# PET_Diag_Clip.net
KiCad netlist of a schematic drawn in EAGLE
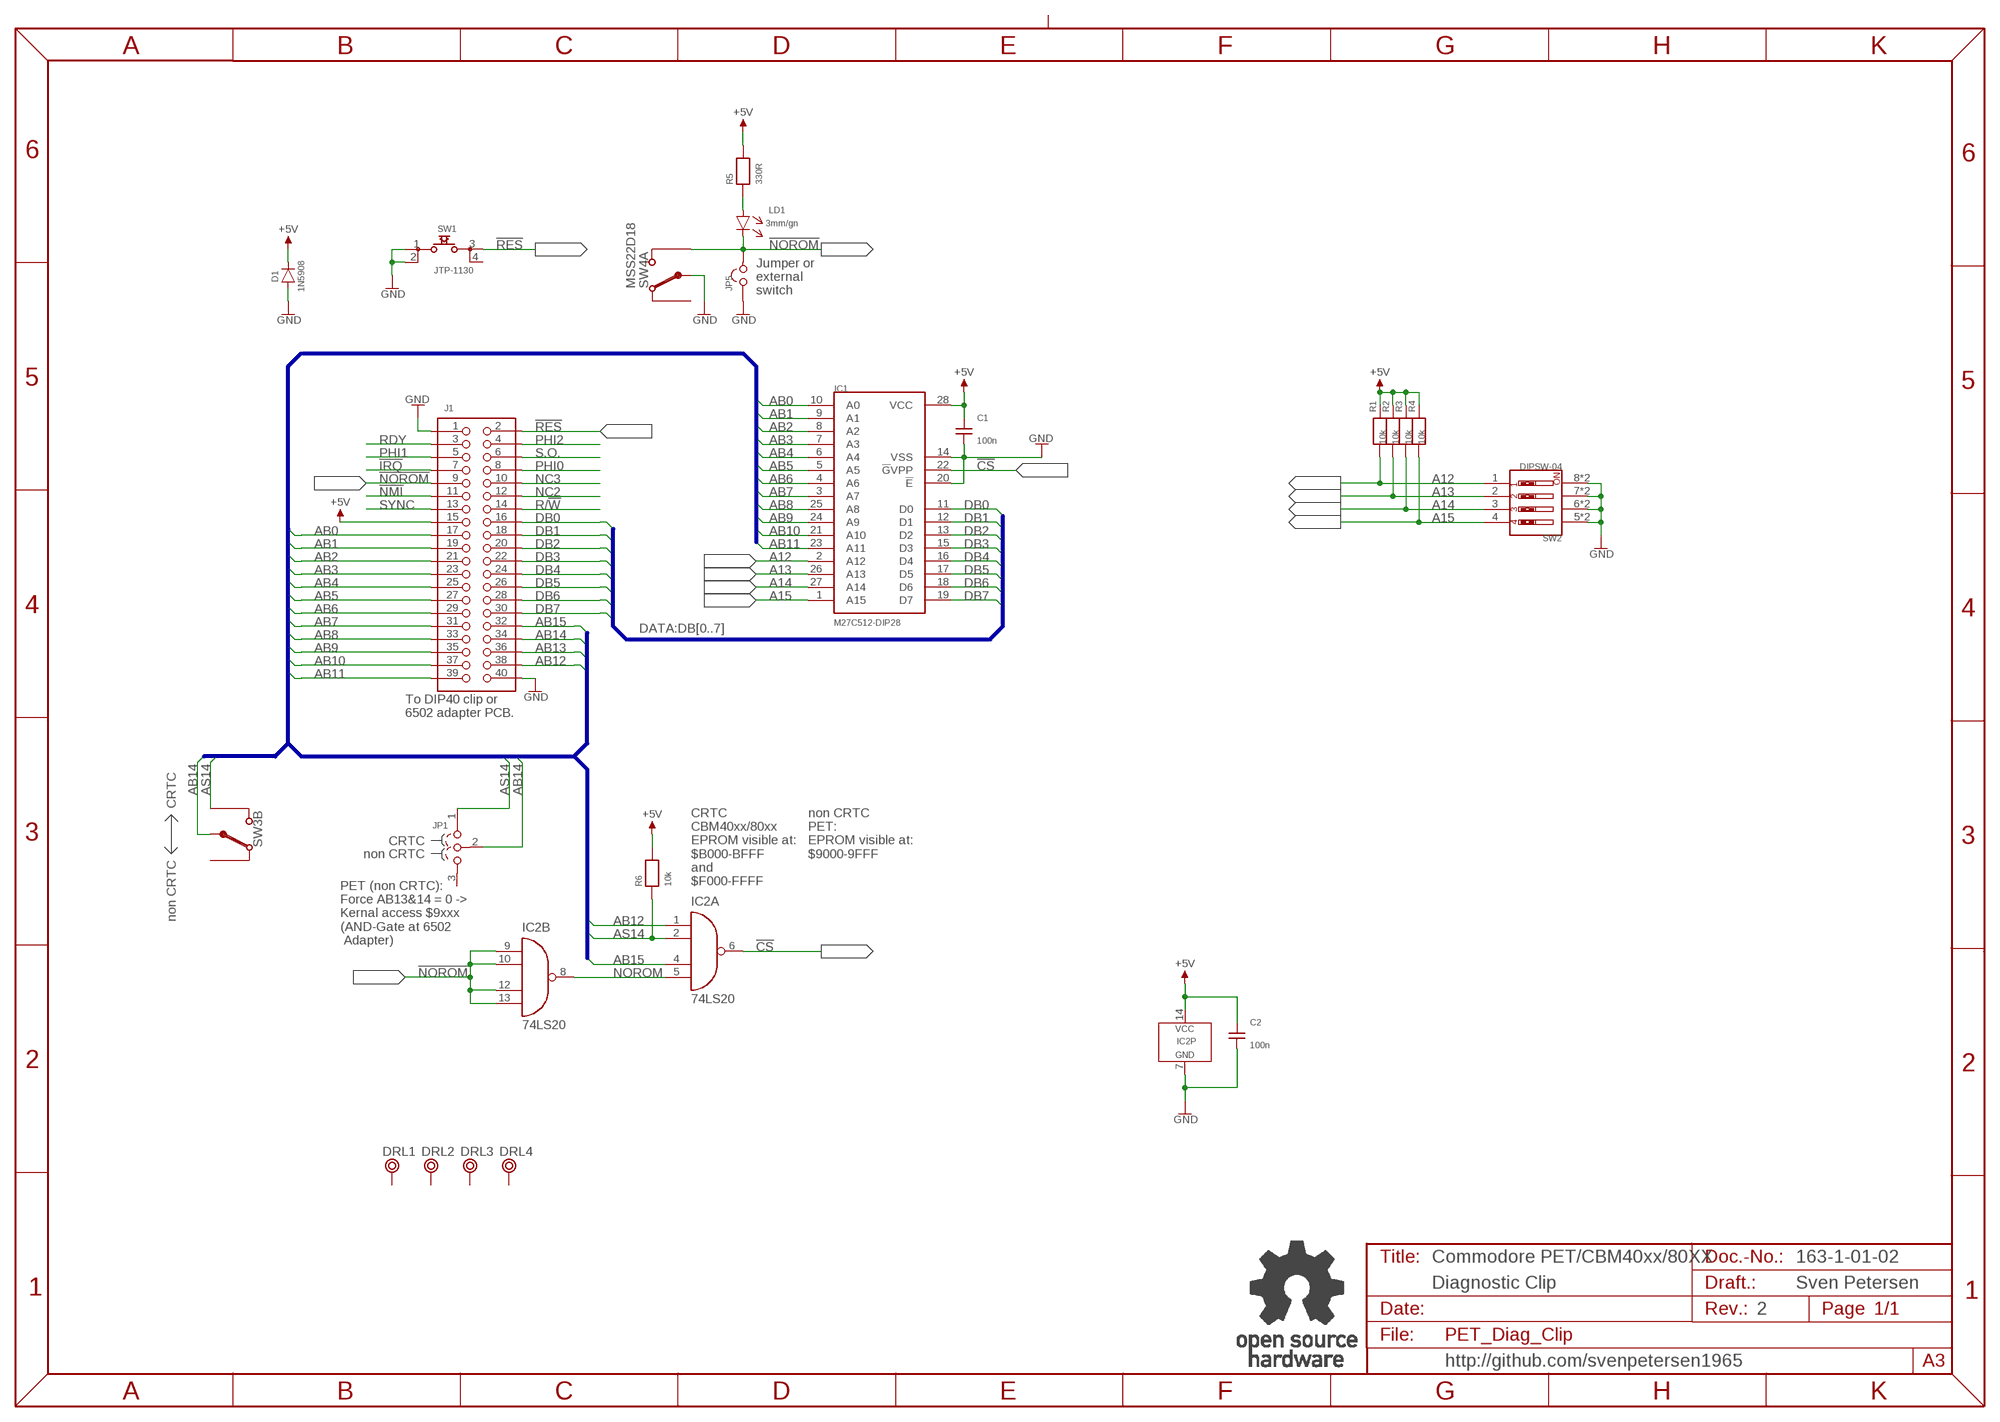
[diagram p0: schematic, sheet 1]

(export (version "E")
  (design (tool "Eeschema 10.0.6"))
  (components
    (comp (ref "C1")
      (value "100n")
      (footprint "eagle-import:C-2,5")
      (libsource (lib "eagle-import") (part "CAP01"))
    )
    (comp (ref "C2")
      (value "100n")
      (footprint "eagle-import:C-2,5")
      (libsource (lib "eagle-import") (part "CAP01"))
    )
    (comp (ref "D1")
      (value "1N5908")
      (footprint "eagle-import:DO-201")
      (libsource (lib "eagle-import") (part "1N5402"))
    )
    (comp (ref "DRL1")
      (value "BOHR3,5")
      (footprint "eagle-import:BOHR3,5")
      (libsource (lib "eagle-import") (part "BOHR3,5"))
    )
    (comp (ref "DRL2")
      (value "BOHR3,5")
      (footprint "eagle-import:BOHR3,5")
      (libsource (lib "eagle-import") (part "BOHR3,5"))
    )
    (comp (ref "DRL3")
      (value "BOHR3,5")
      (footprint "eagle-import:BOHR3,5")
      (libsource (lib "eagle-import") (part "BOHR3,5"))
    )
    (comp (ref "DRL4")
      (value "BOHR3,5")
      (footprint "eagle-import:BOHR3,5")
      (libsource (lib "eagle-import") (part "BOHR3,5"))
    )
    (comp (ref "IC1")
      (value "M27C512-DIP28")
      (footprint "eagle-import:DIL28-6")
      (libsource (lib "eagle-import") (part "M27C512-DIP28"))
    )
    (comp (ref "IC2")
      (value "74LS20")
      (footprint "eagle-import:DIL-14")
      (libsource (lib "eagle-import") (part "7420N"))
    )
    (comp (ref "J1")
      (value "PINHD-2X20WV")
      (footprint "eagle-import:2X20WV")
      (libsource (lib "eagle-import") (part "PINHD-2X20WV"))
    )
    (comp (ref "JP1")
      (value "COMBI-3P")
      (footprint "eagle-import:COMBI-3P")
      (libsource (lib "eagle-import") (part "COMBI-3P"))
    )
    (comp (ref "JP5")
      (value "JUMPER")
      (footprint "eagle-import:1X02")
      (libsource (lib "eagle-import") (part "JUMPER"))
    )
    (comp (ref "LD1")
      (value "3mm/gn")
      (footprint "eagle-import:3MM")
      (libsource (lib "eagle-import") (part "3MM"))
    )
    (comp (ref "R1")
      (value "10k")
      (footprint "eagle-import:R-10")
      (libsource (lib "eagle-import") (part "RES04"))
    )
    (comp (ref "R2")
      (value "10k")
      (footprint "eagle-import:R-10")
      (libsource (lib "eagle-import") (part "RES04"))
    )
    (comp (ref "R3")
      (value "10k")
      (footprint "eagle-import:R-10")
      (libsource (lib "eagle-import") (part "RES04"))
    )
    (comp (ref "R4")
      (value "10k")
      (footprint "eagle-import:R-10")
      (libsource (lib "eagle-import") (part "RES04"))
    )
    (comp (ref "R5")
      (value "330R")
      (footprint "eagle-import:R-10")
      (libsource (lib "eagle-import") (part "RES04"))
    )
    (comp (ref "R6")
      (value "10k")
      (footprint "eagle-import:R-10")
      (libsource (lib "eagle-import") (part "RES04"))
    )
    (comp (ref "SW1")
      (value "JTP-1130")
      (footprint "eagle-import:JTP-1130")
      (libsource (lib "eagle-import") (part "JTP-1130"))
    )
    (comp (ref "SW2")
      (value "DIPSW-04")
      (footprint "eagle-import:DIPSW-04V-COMBI")
      (libsource (lib "eagle-import") (part "DIPSW-04"))
    )
    (comp (ref "SW3")
      (value "MSS22D18")
      (footprint "eagle-import:DPDT_9MM")
      (libsource (lib "eagle-import") (part "DPDT_9MM"))
    )
    (comp (ref "SW4")
      (value "MSS22D18")
      (footprint "eagle-import:DPDT_9MM")
      (libsource (lib "eagle-import") (part "DPDT_9MM"))
    )
    (comp (ref "U$13")
      (value "OPEN_SOURCE_HW")
      (footprint "eagle-import:OPENHW")
      (libsource (lib "eagle-import") (part "OPEN_SOURCE_HW"))
    )
  )
  (nets
    (net (code "9") (name "+5V") (class "Default")
      (node (ref "C1") (pin "2") (pinfunction "2_2") (pintype "passive"))
      (node (ref "C2") (pin "2") (pinfunction "2_2") (pintype "passive"))
      (node (ref "D1") (pin "K") (pinfunction "K_K") (pintype "passive"))
      (node (ref "IC1") (pin "28") (pinfunction "VCC_28") (pintype "power_in"))
      (node (ref "IC2") (pin "14") (pinfunction "VCC_14") (pintype "bidirectional"))
      (node (ref "J1") (pin "15") (pinfunction "15_15") (pintype "passive"))
      (node (ref "R1") (pin "1") (pinfunction "1_1") (pintype "passive"))
      (node (ref "R2") (pin "1") (pinfunction "1_1") (pintype "passive"))
      (node (ref "R3") (pin "1") (pinfunction "1_1") (pintype "passive"))
      (node (ref "R4") (pin "1") (pinfunction "1_1") (pintype "passive"))
      (node (ref "R5") (pin "2") (pinfunction "2_2") (pintype "passive"))
      (node (ref "R6") (pin "2") (pinfunction "2_2") (pintype "passive"))
    )
    (net (code "10") (name "/A12") (class "Default")
      (node (ref "IC1") (pin "2") (pinfunction "A12_2") (pintype "input"))
      (node (ref "R1") (pin "2") (pinfunction "2_2") (pintype "passive"))
      (node (ref "SW2") (pin "1") (pinfunction "1_1") (pintype "passive"))
    )
    (net (code "11") (name "/A13") (class "Default")
      (node (ref "IC1") (pin "26") (pinfunction "A13_26") (pintype "input"))
      (node (ref "R2") (pin "2") (pinfunction "2_2") (pintype "passive"))
      (node (ref "SW2") (pin "2") (pinfunction "2_2") (pintype "passive"))
    )
    (net (code "12") (name "/A14") (class "Default")
      (node (ref "IC1") (pin "27") (pinfunction "A14_27") (pintype "input"))
      (node (ref "R3") (pin "2") (pinfunction "2_2") (pintype "passive"))
      (node (ref "SW2") (pin "3") (pinfunction "3_3") (pintype "passive"))
    )
    (net (code "13") (name "/A15") (class "Default")
      (node (ref "IC1") (pin "1") (pinfunction "A15_1") (pintype "input"))
      (node (ref "R4") (pin "2") (pinfunction "2_2") (pintype "passive"))
      (node (ref "SW2") (pin "4") (pinfunction "4_4") (pintype "passive"))
    )
    (net (code "14") (name "/AB0") (class "Default")
      (node (ref "IC1") (pin "10") (pinfunction "A0_10") (pintype "input"))
      (node (ref "J1") (pin "17") (pinfunction "17_17") (pintype "passive"))
    )
    (net (code "15") (name "/AB1") (class "Default")
      (node (ref "IC1") (pin "9") (pinfunction "A1_9") (pintype "input"))
      (node (ref "J1") (pin "19") (pinfunction "19_19") (pintype "passive"))
    )
    (net (code "16") (name "/AB2") (class "Default")
      (node (ref "IC1") (pin "8") (pinfunction "A2_8") (pintype "input"))
      (node (ref "J1") (pin "21") (pinfunction "21_21") (pintype "passive"))
    )
    (net (code "17") (name "/AB3") (class "Default")
      (node (ref "IC1") (pin "7") (pinfunction "A3_7") (pintype "input"))
      (node (ref "J1") (pin "23") (pinfunction "23_23") (pintype "passive"))
    )
    (net (code "18") (name "/AB4") (class "Default")
      (node (ref "IC1") (pin "6") (pinfunction "A4_6") (pintype "input"))
      (node (ref "J1") (pin "25") (pinfunction "25_25") (pintype "passive"))
    )
    (net (code "19") (name "/AB5") (class "Default")
      (node (ref "IC1") (pin "5") (pinfunction "A5_5") (pintype "input"))
      (node (ref "J1") (pin "27") (pinfunction "27_27") (pintype "passive"))
    )
    (net (code "20") (name "/AB6") (class "Default")
      (node (ref "IC1") (pin "4") (pinfunction "A6_4") (pintype "input"))
      (node (ref "J1") (pin "29") (pinfunction "29_29") (pintype "passive"))
    )
    (net (code "21") (name "/AB7") (class "Default")
      (node (ref "IC1") (pin "3") (pinfunction "A7_3") (pintype "input"))
      (node (ref "J1") (pin "31") (pinfunction "31_31") (pintype "passive"))
    )
    (net (code "22") (name "/AB8") (class "Default")
      (node (ref "IC1") (pin "25") (pinfunction "A8_25") (pintype "input"))
      (node (ref "J1") (pin "33") (pinfunction "33_33") (pintype "passive"))
    )
    (net (code "23") (name "/AB9") (class "Default")
      (node (ref "IC1") (pin "24") (pinfunction "A9_24") (pintype "input"))
      (node (ref "J1") (pin "35") (pinfunction "35_35") (pintype "passive"))
    )
    (net (code "24") (name "/AB10") (class "Default")
      (node (ref "IC1") (pin "21") (pinfunction "A10_21") (pintype "input"))
      (node (ref "J1") (pin "37") (pinfunction "37_37") (pintype "passive"))
    )
    (net (code "25") (name "/AB11") (class "Default")
      (node (ref "IC1") (pin "23") (pinfunction "A11_23") (pintype "input"))
      (node (ref "J1") (pin "39") (pinfunction "39_39") (pintype "passive"))
    )
    (net (code "26") (name "/AB12") (class "Default")
      (node (ref "IC2") (pin "1") (pinfunction "I0_1") (pintype "input"))
      (node (ref "J1") (pin "38") (pinfunction "38_38") (pintype "passive"))
    )
    (net (code "27") (name "/AB13") (class "Default")
      (node (ref "J1") (pin "36") (pinfunction "36_36") (pintype "passive"))
    )
    (net (code "28") (name "/AB14") (class "Default")
      (node (ref "J1") (pin "34") (pinfunction "34_34") (pintype "passive"))
      (node (ref "JP1") (pin "2") (pinfunction "2_2") (pintype "bidirectional"))
      (node (ref "SW3") (pin "5") (pinfunction "COM_5") (pintype "bidirectional"))
    )
    (net (code "29") (name "/AB15") (class "Default")
      (node (ref "IC2") (pin "4") (pinfunction "I2_4") (pintype "input"))
      (node (ref "J1") (pin "32") (pinfunction "32_32") (pintype "passive"))
    )
    (net (code "30") (name "/AS14") (class "Default")
      (node (ref "IC2") (pin "2") (pinfunction "I1_2") (pintype "input"))
      (node (ref "JP1") (pin "1") (pinfunction "1_1") (pintype "bidirectional"))
      (node (ref "R6") (pin "1") (pinfunction "1_1") (pintype "passive"))
      (node (ref "SW3") (pin "6") (pinfunction "UP_6") (pintype "bidirectional"))
    )
    (net (code "32") (name "/DB0") (class "Default")
      (node (ref "IC1") (pin "11") (pinfunction "D0_11") (pintype "bidirectional"))
      (node (ref "J1") (pin "16") (pinfunction "16_16") (pintype "passive"))
    )
    (net (code "33") (name "/DB1") (class "Default")
      (node (ref "IC1") (pin "12") (pinfunction "D1_12") (pintype "bidirectional"))
      (node (ref "J1") (pin "18") (pinfunction "18_18") (pintype "passive"))
    )
    (net (code "34") (name "/DB2") (class "Default")
      (node (ref "IC1") (pin "13") (pinfunction "D2_13") (pintype "bidirectional"))
      (node (ref "J1") (pin "20") (pinfunction "20_20") (pintype "passive"))
    )
    (net (code "35") (name "/DB3") (class "Default")
      (node (ref "IC1") (pin "15") (pinfunction "D3_15") (pintype "bidirectional"))
      (node (ref "J1") (pin "22") (pinfunction "22_22") (pintype "passive"))
    )
    (net (code "36") (name "/DB4") (class "Default")
      (node (ref "IC1") (pin "16") (pinfunction "D4_16") (pintype "bidirectional"))
      (node (ref "J1") (pin "24") (pinfunction "24_24") (pintype "passive"))
    )
    (net (code "37") (name "/DB5") (class "Default")
      (node (ref "IC1") (pin "17") (pinfunction "D5_17") (pintype "bidirectional"))
      (node (ref "J1") (pin "26") (pinfunction "26_26") (pintype "passive"))
    )
    (net (code "38") (name "/DB6") (class "Default")
      (node (ref "IC1") (pin "18") (pinfunction "D6_18") (pintype "bidirectional"))
      (node (ref "J1") (pin "28") (pinfunction "28_28") (pintype "passive"))
    )
    (net (code "39") (name "/DB7") (class "Default")
      (node (ref "IC1") (pin "19") (pinfunction "D7_19") (pintype "bidirectional"))
      (node (ref "J1") (pin "30") (pinfunction "30_30") (pintype "passive"))
    )
    (net (code "40") (name "/NC2") (class "Default")
      (node (ref "J1") (pin "12") (pinfunction "12_12") (pintype "passive"))
    )
    (net (code "41") (name "/NC3") (class "Default")
      (node (ref "J1") (pin "10") (pinfunction "10_10") (pintype "passive"))
    )
    (net (code "42") (name "/NOROM") (class "Default")
      (node (ref "IC2") (pin "5") (pinfunction "I3_5") (pintype "input"))
      (node (ref "IC2") (pin "8") (pinfunction "O_8") (pintype "output"))
    )
    (net (code "43") (name "/PHI0") (class "Default")
      (node (ref "J1") (pin "8") (pinfunction "8_8") (pintype "passive"))
    )
    (net (code "44") (name "/PHI1") (class "Default")
      (node (ref "J1") (pin "5") (pinfunction "5_5") (pintype "passive"))
    )
    (net (code "45") (name "/PHI2") (class "Default")
      (node (ref "J1") (pin "4") (pinfunction "4_4") (pintype "passive"))
    )
    (net (code "46") (name "/RDY") (class "Default")
      (node (ref "J1") (pin "3") (pinfunction "3_3") (pintype "passive"))
    )
    (net (code "47") (name "/R{slash}~{W}") (class "Default")
      (node (ref "J1") (pin "14") (pinfunction "14_14") (pintype "passive"))
    )
    (net (code "48") (name "/S.O.") (class "Default")
      (node (ref "J1") (pin "6") (pinfunction "6_6") (pintype "passive"))
    )
    (net (code "49") (name "/SYNC") (class "Default")
      (node (ref "J1") (pin "13") (pinfunction "13_13") (pintype "passive"))
    )
    (net (code "50") (name "/~{CS}") (class "Default")
      (node (ref "IC1") (pin "22") (pinfunction "~{G}VPP_22") (pintype "input"))
      (node (ref "IC2") (pin "6") (pinfunction "O_6") (pintype "output"))
    )
    (net (code "51") (name "/~{IRQ}") (class "Default")
      (node (ref "J1") (pin "7") (pinfunction "7_7") (pintype "passive"))
    )
    (net (code "52") (name "/~{NMI}") (class "Default")
      (node (ref "J1") (pin "11") (pinfunction "11_11") (pintype "passive"))
    )
    (net (code "53") (name "/~{NOROM}") (class "Default")
      (node (ref "IC2") (pin "10") (pinfunction "I1_10") (pintype "input"))
      (node (ref "IC2") (pin "12") (pinfunction "I2_12") (pintype "input"))
      (node (ref "IC2") (pin "13") (pinfunction "I3_13") (pintype "input"))
      (node (ref "IC2") (pin "9") (pinfunction "I0_9") (pintype "input"))
      (node (ref "J1") (pin "9") (pinfunction "9_9") (pintype "passive"))
      (node (ref "JP5") (pin "2") (pinfunction "2_2") (pintype "bidirectional"))
      (node (ref "LD1") (pin "C") (pinfunction "K_C") (pintype "bidirectional"))
      (node (ref "SW4") (pin "1") (pinfunction "UP_1") (pintype "bidirectional"))
    )
    (net (code "54") (name "/~{RES}") (class "Default")
      (node (ref "J1") (pin "2") (pinfunction "2_2") (pintype "passive"))
      (node (ref "SW1") (pin "3") (pinfunction "3_3") (pintype "passive"))
    )
    (net (code "55") (name "GND") (class "Default")
      (node (ref "C1") (pin "1") (pinfunction "1_1") (pintype "passive"))
      (node (ref "C2") (pin "1") (pinfunction "1_1") (pintype "passive"))
      (node (ref "D1") (pin "A") (pinfunction "A_A") (pintype "passive"))
      (node (ref "IC1") (pin "14") (pinfunction "VSS_14") (pintype "power_in"))
      (node (ref "IC1") (pin "20") (pinfunction "~{E}_20") (pintype "input"))
      (node (ref "IC2") (pin "7") (pinfunction "GND_7") (pintype "bidirectional"))
      (node (ref "J1") (pin "1") (pinfunction "1_1") (pintype "passive"))
      (node (ref "J1") (pin "40") (pinfunction "40_40") (pintype "passive"))
      (node (ref "JP5") (pin "1") (pinfunction "1_1") (pintype "bidirectional"))
      (node (ref "SW1") (pin "1") (pinfunction "1_1") (pintype "passive"))
      (node (ref "SW1") (pin "2") (pinfunction "2_2") (pintype "passive"))
      (node (ref "SW2") (pin "5") (pinfunction "5_5") (pintype "passive"))
      (node (ref "SW2") (pin "5A") (pinfunction "5_5A") (pintype "passive"))
      (node (ref "SW2") (pin "6") (pinfunction "6_6") (pintype "passive"))
      (node (ref "SW2") (pin "6A") (pinfunction "6_6A") (pintype "passive"))
      (node (ref "SW2") (pin "7") (pinfunction "7_7") (pintype "passive"))
      (node (ref "SW2") (pin "7A") (pinfunction "7_7A") (pintype "passive"))
      (node (ref "SW2") (pin "8") (pinfunction "8_8") (pintype "passive"))
      (node (ref "SW2") (pin "8A") (pinfunction "8_8A") (pintype "passive"))
      (node (ref "SW4") (pin "2") (pinfunction "COM_2") (pintype "bidirectional"))
    )
    (net (code "56") (name "Net-(LD1-PadA)") (class "Default")
      (node (ref "LD1") (pin "A") (pinfunction "A_A") (pintype "bidirectional"))
      (node (ref "R5") (pin "1") (pinfunction "1_1") (pintype "passive"))
    )
    (net (code "57") (name "unconnected-(DRL1-PadP$1)") (class "Default")
      (node (ref "DRL1") (pin "P$1") (pinfunction "P$1_P$1") (pintype "passive"))
    )
    (net (code "58") (name "unconnected-(DRL2-PadP$1)") (class "Default")
      (node (ref "DRL2") (pin "P$1") (pinfunction "P$1_P$1") (pintype "passive"))
    )
    (net (code "59") (name "unconnected-(DRL3-PadP$1)") (class "Default")
      (node (ref "DRL3") (pin "P$1") (pinfunction "P$1_P$1") (pintype "passive"))
    )
    (net (code "60") (name "unconnected-(DRL4-PadP$1)") (class "Default")
      (node (ref "DRL4") (pin "P$1") (pinfunction "P$1_P$1") (pintype "passive"))
    )
    (net (code "61") (name "unconnected-(JP1-Pad3)") (class "Default")
      (node (ref "JP1") (pin "3") (pinfunction "3_3") (pintype "bidirectional"))
    )
    (net (code "62") (name "unconnected-(SW1-Pad4)") (class "Default")
      (node (ref "SW1") (pin "4") (pinfunction "4_4") (pintype "passive"))
    )
    (net (code "63") (name "unconnected-(SW3B-DWN-Pad4)") (class "Default")
      (node (ref "SW3") (pin "4") (pinfunction "DWN_4") (pintype "bidirectional"))
    )
    (net (code "64") (name "unconnected-(SW4A-DWN-Pad3)") (class "Default")
      (node (ref "SW4") (pin "3") (pinfunction "DWN_3") (pintype "bidirectional"))
    )
  )
)
